# CH340S25P-R0.net
KiCad netlist of a schematic drawn in Altium Designer
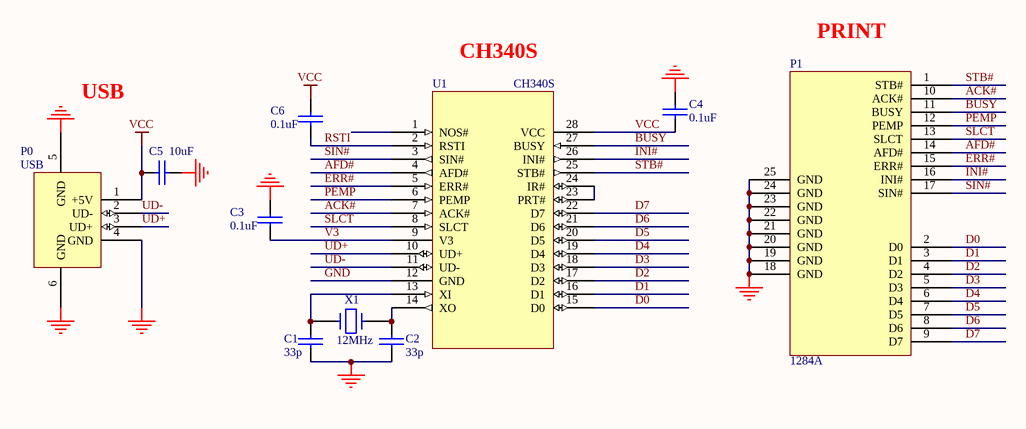
[diagram p0: CH340S25P-R0.SchDoc]

(export (version "E")
  (design (tool "Eeschema 10.0.6"))
  (components
    (comp (ref "C1") (value "33p") (footprint "0603") (libsource (lib "*") (part "CAP")))
    (comp (ref "C2") (value "33p") (footprint "0603") (libsource (lib "*") (part "CAP")))
    (comp (ref "C3") (value "0.1uF") (footprint "0603") (libsource (lib "*") (part "CAP")))
    (comp (ref "C4")
      (value "0.1uF")
      (footprint "0603")
      (description "Capacitor")
      (libsource (lib "") (part "CAP_1"))
    )
    (comp (ref "C5")
      (value "10uF")
      (footprint "3216")
      (description "Capacitor")
      (libsource (lib "") (part "CAP_1"))
    )
    (comp (ref "C6") (value "0.1uF") (footprint "0603") (libsource (lib "*") (part "CAP")))
    (comp (ref "P0") (value "USB") (footprint "SIP04") (libsource (lib "*") (part "USB")))
    (comp (ref "P1") (value "1284A") (footprint "1284A-DB25") (libsource (lib "*") (part "1284A")))
    (comp (ref "U1") (value "CH340S") (footprint "SOP28") (libsource (lib "*") (part "CH340S_P")))
    (comp (ref "X1")
      (value "12MHz")
      (footprint "XTAL1")
      (description "Crystal")
      (libsource (lib "*") (part "CRYSTAL"))
    )
  )
  (nets
    (net (code "1") (name "/ACK#") (class "Default")
      (node (ref "P1") (pin "10") (pinfunction "ACK#_10") (pintype "passive"))
      (node (ref "U1") (pin "7") (pinfunction "ACK#_7") (pintype "input"))
    )
    (net (code "2") (name "/AFD#") (class "Default")
      (node (ref "P1") (pin "14") (pinfunction "AFD#_14") (pintype "passive"))
      (node (ref "U1") (pin "4") (pinfunction "AFD#_4") (pintype "output"))
    )
    (net (code "3") (name "/BUSY") (class "Default")
      (node (ref "P1") (pin "11") (pinfunction "BUSY_11") (pintype "passive"))
      (node (ref "U1") (pin "27") (pinfunction "BUSY_27") (pintype "input"))
    )
    (net (code "4") (name "/D0") (class "Default")
      (node (ref "P1") (pin "2") (pinfunction "D0_2") (pintype "passive"))
      (node (ref "U1") (pin "15") (pinfunction "D0_15") (pintype "bidirectional"))
    )
    (net (code "5") (name "/D1") (class "Default")
      (node (ref "P1") (pin "3") (pinfunction "D1_3") (pintype "passive"))
      (node (ref "U1") (pin "16") (pinfunction "D1_16") (pintype "bidirectional"))
    )
    (net (code "6") (name "/D2") (class "Default")
      (node (ref "P1") (pin "4") (pinfunction "D2_4") (pintype "passive"))
      (node (ref "U1") (pin "17") (pinfunction "D2_17") (pintype "bidirectional"))
    )
    (net (code "7") (name "/D3") (class "Default")
      (node (ref "P1") (pin "5") (pinfunction "D3_5") (pintype "passive"))
      (node (ref "U1") (pin "18") (pinfunction "D3_18") (pintype "bidirectional"))
    )
    (net (code "8") (name "/D4") (class "Default")
      (node (ref "P1") (pin "6") (pinfunction "D4_6") (pintype "passive"))
      (node (ref "U1") (pin "19") (pinfunction "D4_19") (pintype "bidirectional"))
    )
    (net (code "9") (name "/D5") (class "Default")
      (node (ref "P1") (pin "7") (pinfunction "D5_7") (pintype "passive"))
      (node (ref "U1") (pin "20") (pinfunction "D5_20") (pintype "bidirectional"))
    )
    (net (code "10") (name "/D6") (class "Default")
      (node (ref "P1") (pin "8") (pinfunction "D6_8") (pintype "passive"))
      (node (ref "U1") (pin "21") (pinfunction "D6_21") (pintype "bidirectional"))
    )
    (net (code "11") (name "/D7") (class "Default")
      (node (ref "P1") (pin "9") (pinfunction "D7_9") (pintype "passive"))
      (node (ref "U1") (pin "22") (pinfunction "D7_22") (pintype "bidirectional"))
    )
    (net (code "12") (name "/ERR#") (class "Default")
      (node (ref "P1") (pin "15") (pinfunction "ERR#_15") (pintype "passive"))
      (node (ref "U1") (pin "5") (pinfunction "ERR#_5") (pintype "input"))
    )
    (net (code "13") (name "/INI#") (class "Default")
      (node (ref "P1") (pin "16") (pinfunction "INI#_16") (pintype "passive"))
      (node (ref "U1") (pin "26") (pinfunction "INI#_26") (pintype "output"))
    )
    (net (code "14") (name "/PEMP") (class "Default")
      (node (ref "P1") (pin "12") (pinfunction "PEMP_12") (pintype "passive"))
      (node (ref "U1") (pin "6") (pinfunction "PEMP_6") (pintype "input"))
    )
    (net (code "15") (name "/RSTI") (class "Default")
      (node (ref "C6") (pin "2") (pintype "passive"))
      (node (ref "U1") (pin "2") (pinfunction "RSTI_2") (pintype "input"))
    )
    (net (code "16") (name "/SIN#") (class "Default")
      (node (ref "P1") (pin "17") (pinfunction "SIN#_17") (pintype "passive"))
      (node (ref "U1") (pin "3") (pinfunction "SIN#_3") (pintype "output"))
    )
    (net (code "17") (name "/SLCT") (class "Default")
      (node (ref "P1") (pin "13") (pinfunction "SLCT_13") (pintype "passive"))
      (node (ref "U1") (pin "8") (pinfunction "SLCT_8") (pintype "input"))
    )
    (net (code "18") (name "/STB#") (class "Default")
      (node (ref "P1") (pin "1") (pinfunction "STB#_1") (pintype "passive"))
      (node (ref "U1") (pin "25") (pinfunction "STB#_25") (pintype "output"))
    )
    (net (code "19") (name "/UD+") (class "Default")
      (node (ref "P0") (pin "3") (pinfunction "UD+_3") (pintype "bidirectional"))
      (node (ref "U1") (pin "10") (pinfunction "UD+_10") (pintype "bidirectional"))
    )
    (net (code "20") (name "/UD-") (class "Default")
      (node (ref "P0") (pin "2") (pinfunction "UD-_2") (pintype "bidirectional"))
      (node (ref "U1") (pin "11") (pinfunction "UD-_11") (pintype "bidirectional"))
    )
    (net (code "21") (name "/V3") (class "Default")
      (node (ref "C3") (pin "1") (pintype "passive"))
      (node (ref "U1") (pin "9") (pinfunction "V3_9") (pintype "power_in"))
    )
    (net (code "22") (name "GND") (class "Default")
      (node (ref "C1") (pin "1") (pintype "passive"))
      (node (ref "C2") (pin "1") (pintype "passive"))
      (node (ref "C3") (pin "2") (pintype "passive"))
      (node (ref "C4") (pin "2") (pinfunction "2_2") (pintype "passive"))
      (node (ref "C5") (pin "2") (pinfunction "2_2") (pintype "passive"))
      (node (ref "P0") (pin "4") (pinfunction "GND_4") (pintype "power_in"))
      (node (ref "P0") (pin "5") (pinfunction "GND_5") (pintype "power_in"))
      (node (ref "P0") (pin "6") (pinfunction "GND_6") (pintype "power_in"))
      (node (ref "P1") (pin "18") (pinfunction "GND_18") (pintype "passive"))
      (node (ref "P1") (pin "19") (pinfunction "GND_19") (pintype "passive"))
      (node (ref "P1") (pin "20") (pinfunction "GND_20") (pintype "passive"))
      (node (ref "P1") (pin "21") (pinfunction "GND_21") (pintype "passive"))
      (node (ref "P1") (pin "22") (pinfunction "GND_22") (pintype "passive"))
      (node (ref "P1") (pin "23") (pinfunction "GND_23") (pintype "passive"))
      (node (ref "P1") (pin "24") (pinfunction "GND_24") (pintype "passive"))
      (node (ref "P1") (pin "25") (pinfunction "GND_25") (pintype "passive"))
      (node (ref "U1") (pin "12") (pinfunction "GND_12") (pintype "power_in"))
    )
    (net (code "23") (name "Net-(U1-IR#)") (class "Default")
      (node (ref "U1") (pin "23") (pinfunction "PRT#_23") (pintype "bidirectional"))
      (node (ref "U1") (pin "24") (pinfunction "IR#_24") (pintype "bidirectional"))
    )
    (net (code "24") (name "Net-(U1-XI)") (class "Default")
      (node (ref "C1") (pin "2") (pintype "passive"))
      (node (ref "U1") (pin "13") (pinfunction "XI_13") (pintype "input"))
      (node (ref "X1") (pin "1") (pinfunction "1_1") (pintype "passive"))
    )
    (net (code "25") (name "Net-(U1-XO)") (class "Default")
      (node (ref "C2") (pin "2") (pintype "passive"))
      (node (ref "U1") (pin "14") (pinfunction "XO_14") (pintype "output"))
      (node (ref "X1") (pin "2") (pinfunction "2_2") (pintype "passive"))
    )
    (net (code "26") (name "VCC") (class "Default")
      (node (ref "C4") (pin "1") (pinfunction "1_1") (pintype "passive"))
      (node (ref "C5") (pin "1") (pinfunction "1_1") (pintype "passive"))
      (node (ref "C6") (pin "1") (pintype "passive"))
      (node (ref "P0") (pin "1") (pinfunction "+5V_1") (pintype "power_in"))
      (node (ref "U1") (pin "28") (pinfunction "VCC_28") (pintype "power_in"))
    )
    (net (code "27") (name "unconnected-(U1-NOS#-Pad1)") (class "Default")
      (node (ref "U1") (pin "1") (pinfunction "NOS#_1") (pintype "input"))
    )
  )
)
